# robot_extension_board.net
KiCad netlist of a schematic drawn in Altium Designer
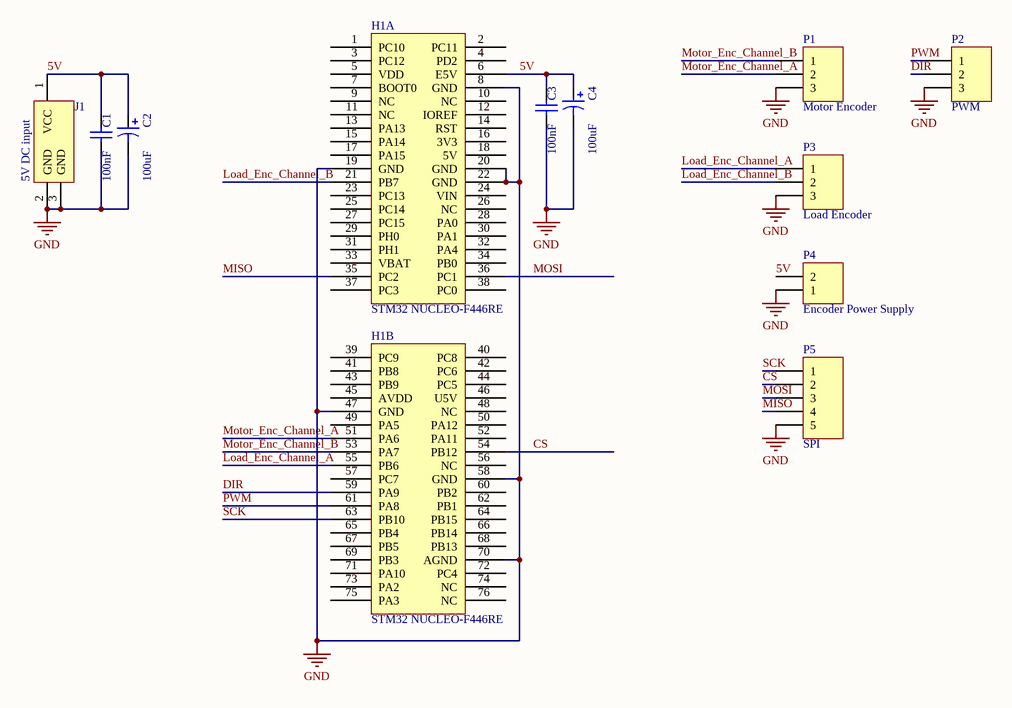
[diagram p0: robot_extension_board.SchDoc]

(export (version "E")
  (design (tool "Eeschema 10.0.6"))
  (components
    (comp (ref "C1")
      (value "100nF")
      (footprint "C_0603")
      (description "Capacitor")
      (fields (field (name "Comment") "Cap") (field (name "PUBLISHER") "Altium Limited"))
      (libsource (lib "Miscellaneous Devices") (part "Cap"))
    )
    (comp (ref "C2")
      (value "100uF")
      (footprint "C_TANTANLUM_E")
      (description "Polarized Capacitor (Radial)")
      (fields (field (name "Comment") "Cap Pol1") (field (name "PUBLISHER") "Altium Limited"))
      (libsource (lib "Miscellaneous Devices") (part "Cap Pol1"))
    )
    (comp (ref "C3")
      (value "100nF")
      (footprint "C_0603")
      (description "Capacitor")
      (fields (field (name "Comment") "Cap") (field (name "PUBLISHER") "Altium Limited"))
      (libsource (lib "Miscellaneous Devices") (part "Cap"))
    )
    (comp (ref "C4")
      (value "100uF")
      (footprint "C_TANTANLUM_E")
      (description "Polarized Capacitor (Radial)")
      (fields (field (name "Comment") "Cap Pol1") (field (name "PUBLISHER") "Altium Limited"))
      (libsource (lib "Miscellaneous Devices") (part "Cap Pol1"))
    )
    (comp (ref "H1")
      (value "STM32 NUCLEO-F446RE")
      (footprint "STM32 NUCLEO 64")
      (libsource (lib "My_lib") (part "STM32 NUCLEO-F446RE"))
    )
    (comp (ref "J1")
      (value "5V DC input")
      (footprint "Female_Barrel_Connector")
      (libsource (lib "My_lib") (part "Female_Barrel_Connector"))
    )
    (comp (ref "P1")
      (value "Motor Encoder")
      (footprint "JST-3-Vertical-2.54mm")
      (description "Header, 3-Pin")
      (fields (field (name "PUBLISHER") "Altium Limited"))
      (libsource (lib "Miscellaneous Connectors") (part "Header 3"))
    )
    (comp (ref "P2")
      (value "PWM")
      (footprint "JST-3-Vertical-2.54mm")
      (description "Header, 3-Pin")
      (fields (field (name "PUBLISHER") "Altium Limited"))
      (libsource (lib "Miscellaneous Connectors") (part "Header 3"))
    )
    (comp (ref "P3")
      (value "Load Encoder")
      (footprint "JST-3-Vertical-2.54mm")
      (description "Header, 3-Pin")
      (fields (field (name "PUBLISHER") "Altium Limited"))
      (libsource (lib "Miscellaneous Connectors") (part "Header 3"))
    )
    (comp (ref "P4")
      (value "Encoder Power Supply")
      (footprint "JST-2-Vertical-2.54mm")
      (description "Header, 2-Pin")
      (fields (field (name "PUBLISHER") "Altium Limited"))
      (libsource (lib "Miscellaneous Connectors") (part "Header 2"))
    )
    (comp (ref "P5")
      (value "SPI")
      (footprint "JST-5-Vertical-2.54mm")
      (description "Header, 5-Pin")
      (fields (field (name "PUBLISHER") "Altium Limited"))
      (libsource (lib "Miscellaneous Connectors") (part "Header 5"))
    )
  )
  (nets
    (net (code "1") (name "/5V") (class "Default")
      (node (ref "C1") (pin "2") (pinfunction "2_2") (pintype "passive"))
      (node (ref "C2") (pin "1") (pinfunction "1_1") (pintype "passive"))
      (node (ref "C3") (pin "2") (pinfunction "2_2") (pintype "passive"))
      (node (ref "C4") (pin "1") (pinfunction "1_1") (pintype "passive"))
      (node (ref "H1") (pin "6") (pinfunction "E5V_6") (pintype "passive"))
      (node (ref "J1") (pin "1") (pinfunction "VCC_1") (pintype "passive"))
      (node (ref "P4") (pin "2") (pinfunction "2_2") (pintype "passive"))
    )
    (net (code "2") (name "/CS") (class "Default")
      (node (ref "H1") (pin "54") (pinfunction "PB12_54") (pintype "passive"))
      (node (ref "P5") (pin "2") (pinfunction "2_2") (pintype "passive"))
    )
    (net (code "3") (name "/DIR") (class "Default")
      (node (ref "H1") (pin "59") (pinfunction "PA9_59") (pintype "passive"))
      (node (ref "P2") (pin "2") (pinfunction "2_2") (pintype "passive"))
    )
    (net (code "4") (name "/Load_Enc_Channel_A") (class "Default")
      (node (ref "H1") (pin "55") (pinfunction "PB6_55") (pintype "passive"))
      (node (ref "P3") (pin "1") (pinfunction "1_1") (pintype "passive"))
    )
    (net (code "5") (name "/Load_Enc_Channel_B") (class "Default")
      (node (ref "H1") (pin "21") (pinfunction "PB7_21") (pintype "passive"))
      (node (ref "P3") (pin "2") (pinfunction "2_2") (pintype "passive"))
    )
    (net (code "6") (name "/MISO") (class "Default")
      (node (ref "H1") (pin "35") (pinfunction "PC2_35") (pintype "passive"))
      (node (ref "P5") (pin "4") (pinfunction "4_4") (pintype "passive"))
    )
    (net (code "7") (name "/MOSI") (class "Default")
      (node (ref "H1") (pin "36") (pinfunction "PC1_36") (pintype "passive"))
      (node (ref "P5") (pin "3") (pinfunction "3_3") (pintype "passive"))
    )
    (net (code "8") (name "/Motor_Enc_Channel_A") (class "Default")
      (node (ref "H1") (pin "51") (pinfunction "PA6_51") (pintype "passive"))
      (node (ref "P1") (pin "2") (pinfunction "2_2") (pintype "passive"))
    )
    (net (code "9") (name "/Motor_Enc_Channel_B") (class "Default")
      (node (ref "H1") (pin "53") (pinfunction "PA7_53") (pintype "passive"))
      (node (ref "P1") (pin "1") (pinfunction "1_1") (pintype "passive"))
    )
    (net (code "10") (name "/PWM") (class "Default")
      (node (ref "H1") (pin "61") (pinfunction "PA8_61") (pintype "passive"))
      (node (ref "P2") (pin "1") (pinfunction "1_1") (pintype "passive"))
    )
    (net (code "11") (name "/SCK") (class "Default")
      (node (ref "H1") (pin "63") (pinfunction "PB10_63") (pintype "passive"))
      (node (ref "P5") (pin "1") (pinfunction "1_1") (pintype "passive"))
    )
    (net (code "12") (name "GND") (class "Default")
      (node (ref "C1") (pin "1") (pinfunction "1_1") (pintype "passive"))
      (node (ref "C2") (pin "2") (pinfunction "2_2") (pintype "passive"))
      (node (ref "C3") (pin "1") (pinfunction "1_1") (pintype "passive"))
      (node (ref "C4") (pin "2") (pinfunction "2_2") (pintype "passive"))
      (node (ref "H1") (pin "19") (pinfunction "GND_19") (pintype "passive"))
      (node (ref "H1") (pin "20") (pinfunction "GND_20") (pintype "passive"))
      (node (ref "H1") (pin "22") (pinfunction "GND_22") (pintype "passive"))
      (node (ref "H1") (pin "47") (pinfunction "GND_47") (pintype "passive"))
      (node (ref "H1") (pin "58") (pinfunction "GND_58") (pintype "passive"))
      (node (ref "H1") (pin "70") (pinfunction "AGND_70") (pintype "passive"))
      (node (ref "H1") (pin "8") (pinfunction "GND_8") (pintype "passive"))
      (node (ref "J1") (pin "2") (pinfunction "GND_2") (pintype "passive"))
      (node (ref "J1") (pin "3") (pinfunction "GND_3") (pintype "passive"))
      (node (ref "P1") (pin "3") (pinfunction "3_3") (pintype "passive"))
      (node (ref "P2") (pin "3") (pinfunction "3_3") (pintype "passive"))
      (node (ref "P3") (pin "3") (pinfunction "3_3") (pintype "passive"))
      (node (ref "P4") (pin "1") (pinfunction "1_1") (pintype "passive"))
      (node (ref "P5") (pin "5") (pinfunction "5_5") (pintype "passive"))
    )
    (net (code "13") (name "unconnected-(H1A-3V3-Pad16)") (class "Default")
      (node (ref "H1") (pin "16") (pinfunction "3V3_16") (pintype "passive"))
    )
    (net (code "14") (name "unconnected-(H1A-5V-Pad18)") (class "Default")
      (node (ref "H1") (pin "18") (pinfunction "5V_18") (pintype "passive"))
    )
    (net (code "15") (name "unconnected-(H1A-BOOT0-Pad7)") (class "Default")
      (node (ref "H1") (pin "7") (pinfunction "BOOT0_7") (pintype "passive"))
    )
    (net (code "16") (name "unconnected-(H1A-IOREF-Pad12)") (class "Default")
      (node (ref "H1") (pin "12") (pinfunction "IOREF_12") (pintype "passive"))
    )
    (net (code "17") (name "unconnected-(H1A-NC-Pad9)") (class "Default")
      (node (ref "H1") (pin "9") (pinfunction "NC_9") (pintype "passive"))
    )
    (net (code "18") (name "unconnected-(H1A-NC-Pad10)") (class "Default")
      (node (ref "H1") (pin "10") (pinfunction "NC_10") (pintype "passive"))
    )
    (net (code "19") (name "unconnected-(H1A-NC-Pad11)") (class "Default")
      (node (ref "H1") (pin "11") (pinfunction "NC_11") (pintype "passive"))
    )
    (net (code "20") (name "unconnected-(H1A-NC-Pad26)") (class "Default")
      (node (ref "H1") (pin "26") (pinfunction "NC_26") (pintype "passive"))
    )
    (net (code "21") (name "unconnected-(H1A-PA0-Pad28)") (class "Default")
      (node (ref "H1") (pin "28") (pinfunction "PA0_28") (pintype "passive"))
    )
    (net (code "22") (name "unconnected-(H1A-PA1-Pad30)") (class "Default")
      (node (ref "H1") (pin "30") (pinfunction "PA1_30") (pintype "passive"))
    )
    (net (code "23") (name "unconnected-(H1A-PA4-Pad32)") (class "Default")
      (node (ref "H1") (pin "32") (pinfunction "PA4_32") (pintype "passive"))
    )
    (net (code "24") (name "unconnected-(H1A-PA13-Pad13)") (class "Default")
      (node (ref "H1") (pin "13") (pinfunction "PA13_13") (pintype "passive"))
    )
    (net (code "25") (name "unconnected-(H1A-PA14-Pad15)") (class "Default")
      (node (ref "H1") (pin "15") (pinfunction "PA14_15") (pintype "passive"))
    )
    (net (code "26") (name "unconnected-(H1A-PA15-Pad17)") (class "Default")
      (node (ref "H1") (pin "17") (pinfunction "PA15_17") (pintype "passive"))
    )
    (net (code "27") (name "unconnected-(H1A-PB0-Pad34)") (class "Default")
      (node (ref "H1") (pin "34") (pinfunction "PB0_34") (pintype "passive"))
    )
    (net (code "28") (name "unconnected-(H1A-PC0-Pad38)") (class "Default")
      (node (ref "H1") (pin "38") (pinfunction "PC0_38") (pintype "passive"))
    )
    (net (code "29") (name "unconnected-(H1A-PC3-Pad37)") (class "Default")
      (node (ref "H1") (pin "37") (pinfunction "PC3_37") (pintype "passive"))
    )
    (net (code "30") (name "unconnected-(H1A-PC10-Pad1)") (class "Default")
      (node (ref "H1") (pin "1") (pinfunction "PC10_1") (pintype "passive"))
    )
    (net (code "31") (name "unconnected-(H1A-PC11-Pad2)") (class "Default")
      (node (ref "H1") (pin "2") (pinfunction "PC11_2") (pintype "passive"))
    )
    (net (code "32") (name "unconnected-(H1A-PC12-Pad3)") (class "Default")
      (node (ref "H1") (pin "3") (pinfunction "PC12_3") (pintype "passive"))
    )
    (net (code "33") (name "unconnected-(H1A-PC13-Pad23)") (class "Default")
      (node (ref "H1") (pin "23") (pinfunction "PC13_23") (pintype "passive"))
    )
    (net (code "34") (name "unconnected-(H1A-PC14-Pad25)") (class "Default")
      (node (ref "H1") (pin "25") (pinfunction "PC14_25") (pintype "passive"))
    )
    (net (code "35") (name "unconnected-(H1A-PC15-Pad27)") (class "Default")
      (node (ref "H1") (pin "27") (pinfunction "PC15_27") (pintype "passive"))
    )
    (net (code "36") (name "unconnected-(H1A-PD2-Pad4)") (class "Default")
      (node (ref "H1") (pin "4") (pinfunction "PD2_4") (pintype "passive"))
    )
    (net (code "37") (name "unconnected-(H1A-PH0-Pad29)") (class "Default")
      (node (ref "H1") (pin "29") (pinfunction "PH0_29") (pintype "passive"))
    )
    (net (code "38") (name "unconnected-(H1A-PH1-Pad31)") (class "Default")
      (node (ref "H1") (pin "31") (pinfunction "PH1_31") (pintype "passive"))
    )
    (net (code "39") (name "unconnected-(H1A-RST-Pad14)") (class "Default")
      (node (ref "H1") (pin "14") (pinfunction "RST_14") (pintype "passive"))
    )
    (net (code "40") (name "unconnected-(H1A-VBAT-Pad33)") (class "Default")
      (node (ref "H1") (pin "33") (pinfunction "VBAT_33") (pintype "passive"))
    )
    (net (code "41") (name "unconnected-(H1A-VDD-Pad5)") (class "Default")
      (node (ref "H1") (pin "5") (pinfunction "VDD_5") (pintype "passive"))
    )
    (net (code "42") (name "unconnected-(H1A-VIN-Pad24)") (class "Default")
      (node (ref "H1") (pin "24") (pinfunction "VIN_24") (pintype "passive"))
    )
    (net (code "43") (name "unconnected-(H1B-AVDD-Pad45)") (class "Default")
      (node (ref "H1") (pin "45") (pinfunction "AVDD_45") (pintype "passive"))
    )
    (net (code "44") (name "unconnected-(H1B-NC-Pad48)") (class "Default")
      (node (ref "H1") (pin "48") (pinfunction "NC_48") (pintype "passive"))
    )
    (net (code "45") (name "unconnected-(H1B-NC-Pad56)") (class "Default")
      (node (ref "H1") (pin "56") (pinfunction "NC_56") (pintype "passive"))
    )
    (net (code "46") (name "unconnected-(H1B-NC-Pad74)") (class "Default")
      (node (ref "H1") (pin "74") (pinfunction "NC_74") (pintype "passive"))
    )
    (net (code "47") (name "unconnected-(H1B-NC-Pad76)") (class "Default")
      (node (ref "H1") (pin "76") (pinfunction "NC_76") (pintype "passive"))
    )
    (net (code "48") (name "unconnected-(H1B-PA2-Pad73)") (class "Default")
      (node (ref "H1") (pin "73") (pinfunction "PA2_73") (pintype "passive"))
    )
    (net (code "49") (name "unconnected-(H1B-PA3-Pad75)") (class "Default")
      (node (ref "H1") (pin "75") (pinfunction "PA3_75") (pintype "passive"))
    )
    (net (code "50") (name "unconnected-(H1B-PA5-Pad49)") (class "Default")
      (node (ref "H1") (pin "49") (pinfunction "PA5_49") (pintype "passive"))
    )
    (net (code "51") (name "unconnected-(H1B-PA10-Pad71)") (class "Default")
      (node (ref "H1") (pin "71") (pinfunction "PA10_71") (pintype "passive"))
    )
    (net (code "52") (name "unconnected-(H1B-PA11-Pad52)") (class "Default")
      (node (ref "H1") (pin "52") (pinfunction "PA11_52") (pintype "passive"))
    )
    (net (code "53") (name "unconnected-(H1B-PA12-Pad50)") (class "Default")
      (node (ref "H1") (pin "50") (pinfunction "PA12_50") (pintype "passive"))
    )
    (net (code "54") (name "unconnected-(H1B-PB1-Pad62)") (class "Default")
      (node (ref "H1") (pin "62") (pinfunction "PB1_62") (pintype "passive"))
    )
    (net (code "55") (name "unconnected-(H1B-PB2-Pad60)") (class "Default")
      (node (ref "H1") (pin "60") (pinfunction "PB2_60") (pintype "passive"))
    )
    (net (code "56") (name "unconnected-(H1B-PB3-Pad69)") (class "Default")
      (node (ref "H1") (pin "69") (pinfunction "PB3_69") (pintype "passive"))
    )
    (net (code "57") (name "unconnected-(H1B-PB4-Pad65)") (class "Default")
      (node (ref "H1") (pin "65") (pinfunction "PB4_65") (pintype "passive"))
    )
    (net (code "58") (name "unconnected-(H1B-PB5-Pad67)") (class "Default")
      (node (ref "H1") (pin "67") (pinfunction "PB5_67") (pintype "passive"))
    )
    (net (code "59") (name "unconnected-(H1B-PB8-Pad41)") (class "Default")
      (node (ref "H1") (pin "41") (pinfunction "PB8_41") (pintype "passive"))
    )
    (net (code "60") (name "unconnected-(H1B-PB9-Pad43)") (class "Default")
      (node (ref "H1") (pin "43") (pinfunction "PB9_43") (pintype "passive"))
    )
    (net (code "61") (name "unconnected-(H1B-PB13-Pad68)") (class "Default")
      (node (ref "H1") (pin "68") (pinfunction "PB13_68") (pintype "passive"))
    )
    (net (code "62") (name "unconnected-(H1B-PB14-Pad66)") (class "Default")
      (node (ref "H1") (pin "66") (pinfunction "PB14_66") (pintype "passive"))
    )
    (net (code "63") (name "unconnected-(H1B-PB15-Pad64)") (class "Default")
      (node (ref "H1") (pin "64") (pinfunction "PB15_64") (pintype "passive"))
    )
    (net (code "64") (name "unconnected-(H1B-PC4-Pad72)") (class "Default")
      (node (ref "H1") (pin "72") (pinfunction "PC4_72") (pintype "passive"))
    )
    (net (code "65") (name "unconnected-(H1B-PC5-Pad44)") (class "Default")
      (node (ref "H1") (pin "44") (pinfunction "PC5_44") (pintype "passive"))
    )
    (net (code "66") (name "unconnected-(H1B-PC6-Pad42)") (class "Default")
      (node (ref "H1") (pin "42") (pinfunction "PC6_42") (pintype "passive"))
    )
    (net (code "67") (name "unconnected-(H1B-PC7-Pad57)") (class "Default")
      (node (ref "H1") (pin "57") (pinfunction "PC7_57") (pintype "passive"))
    )
    (net (code "68") (name "unconnected-(H1B-PC8-Pad40)") (class "Default")
      (node (ref "H1") (pin "40") (pinfunction "PC8_40") (pintype "passive"))
    )
    (net (code "69") (name "unconnected-(H1B-PC9-Pad39)") (class "Default")
      (node (ref "H1") (pin "39") (pinfunction "PC9_39") (pintype "passive"))
    )
    (net (code "70") (name "unconnected-(H1B-U5V-Pad46)") (class "Default")
      (node (ref "H1") (pin "46") (pinfunction "U5V_46") (pintype "passive"))
    )
  )
)
